# SCH_NetStream_Caravel.net
KiCad netlist of a schematic drawn in EasyEDA
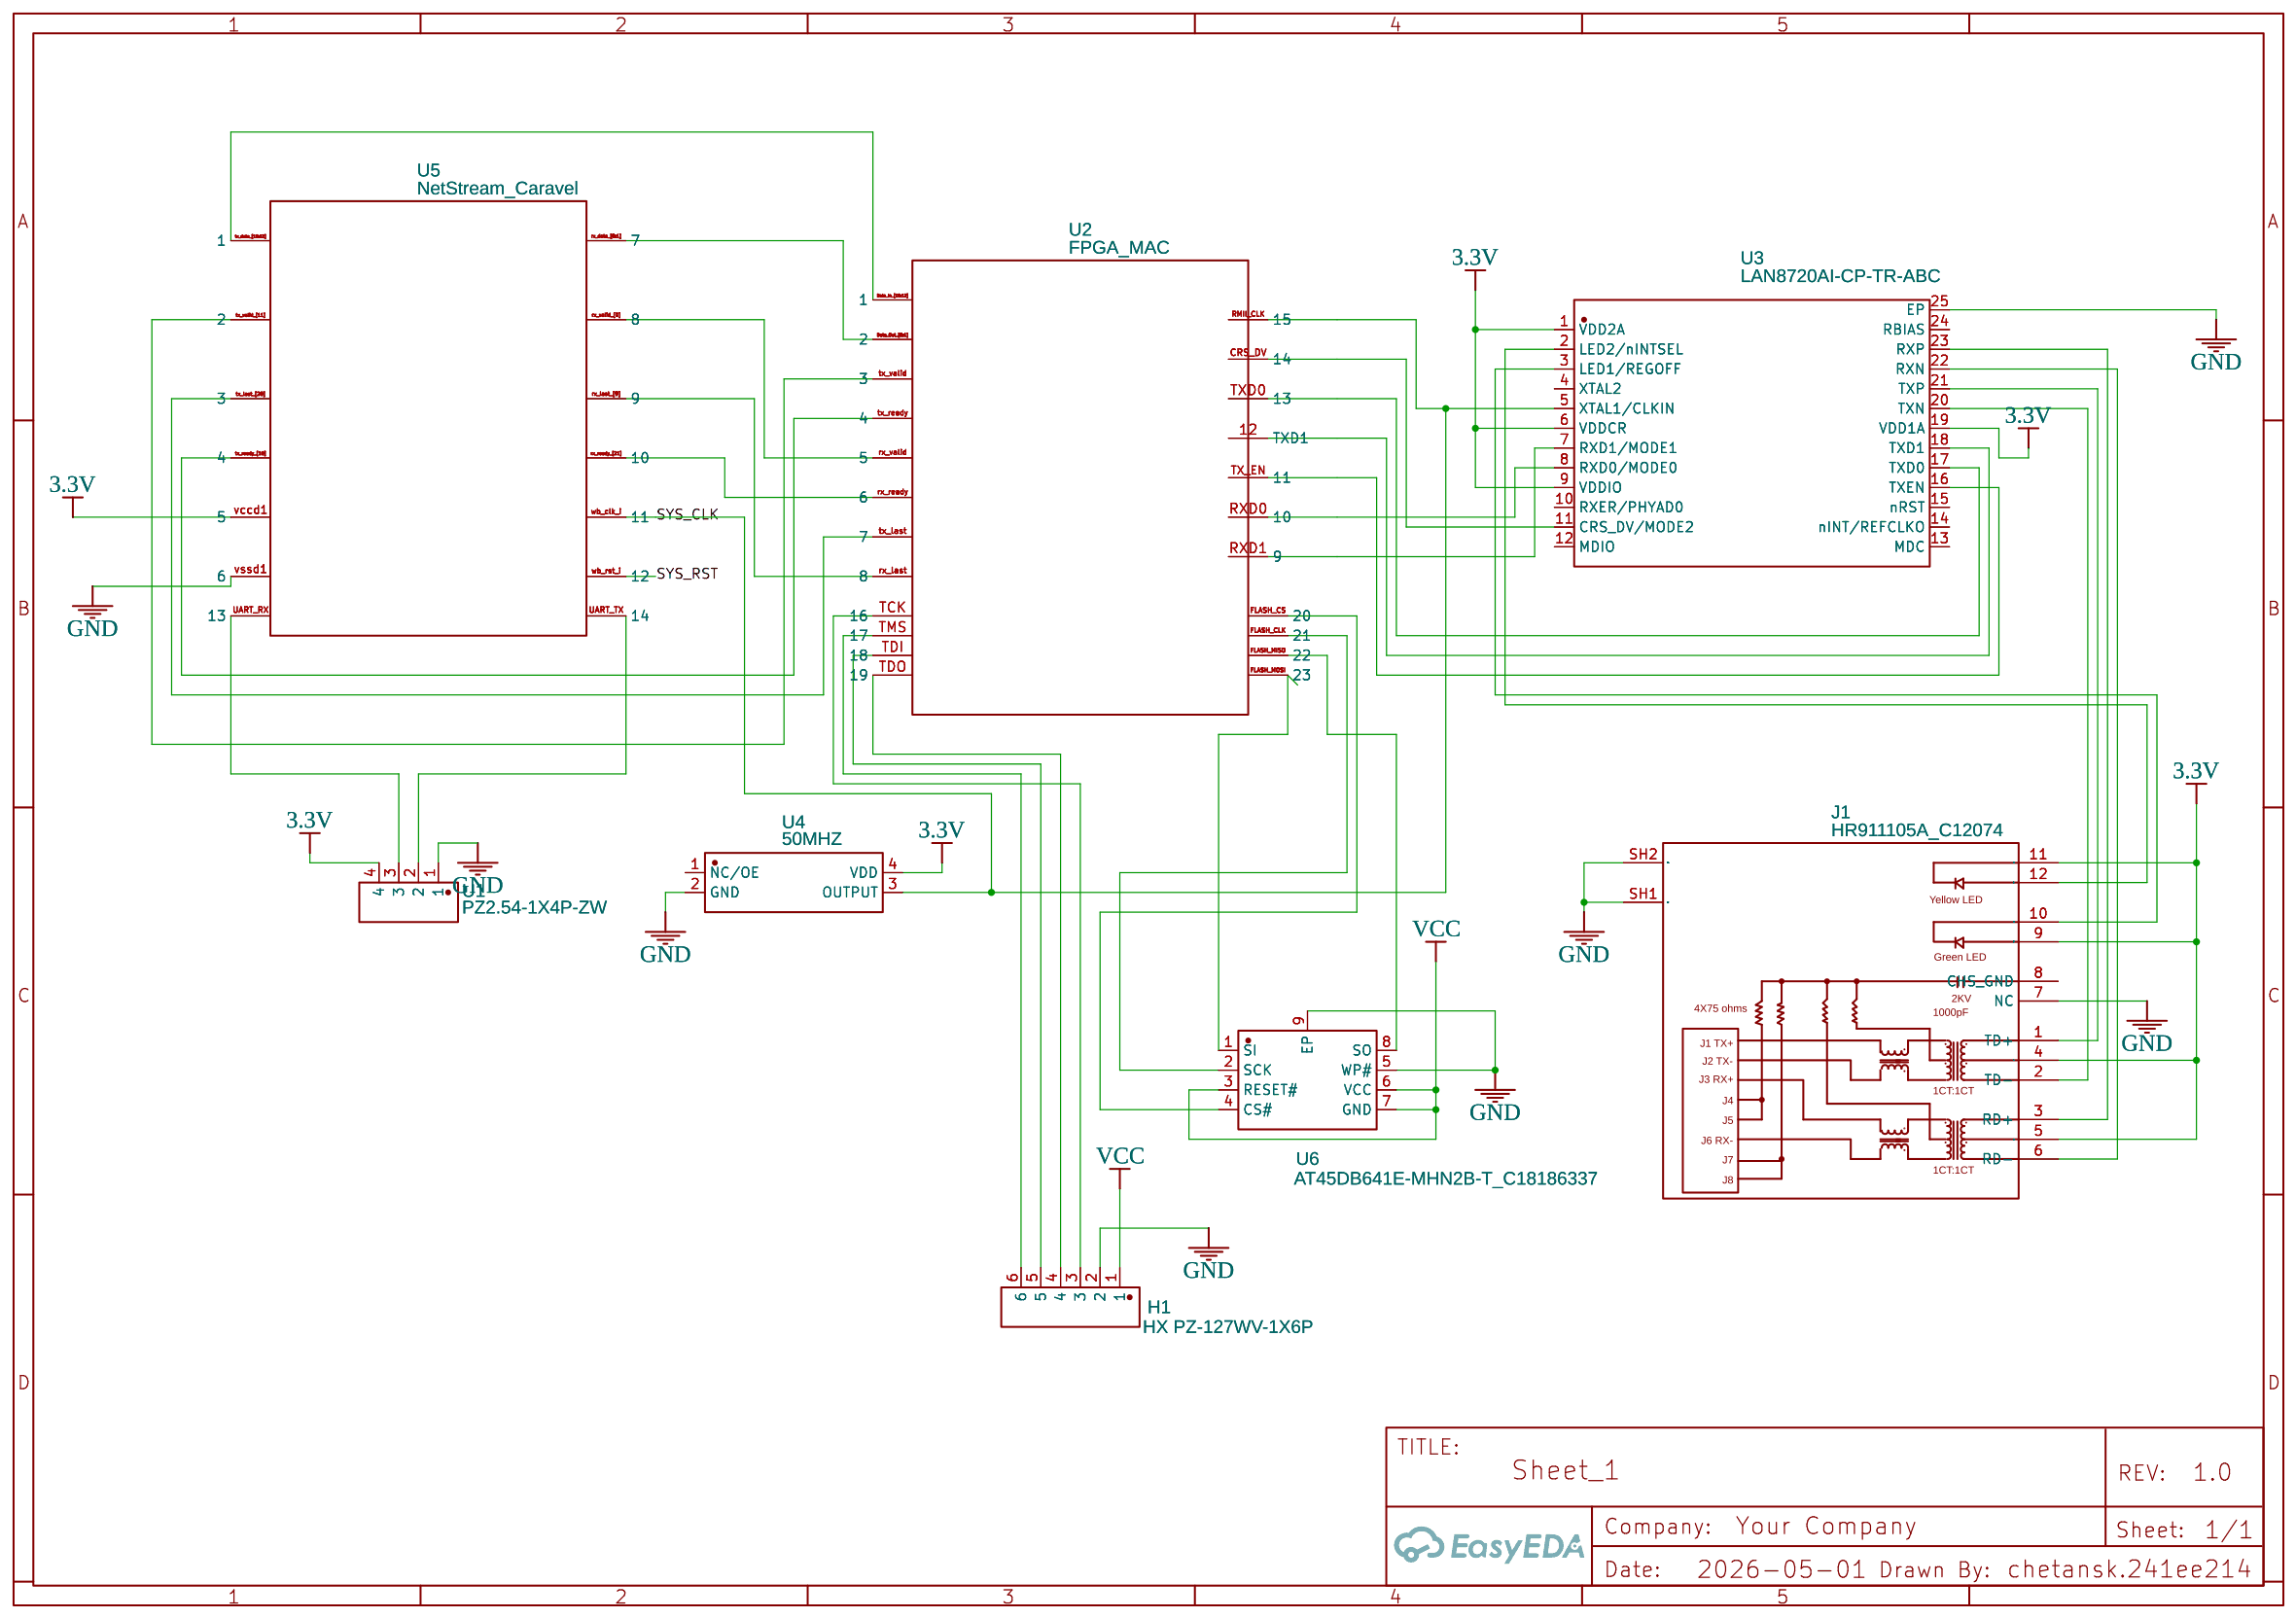
[diagram p0: schematic sheet]

(export (version "E")
  (design (tool "Eeschema 10.0.6"))
  (components
    (comp (ref "H1")
      (value "HX PZ-127WV-1X6P")
      (fields
        (field (name "Manufacturer Part") "HX PZ-127WV-1x6P")
        (field (name "Manufacturer") "hanxia(韩下)")
      )
      (libsource (lib "") (part "HX PZ-127WV-1X6P"))
    )
    (comp (ref "J1")
      (value "HR911105A_C12074")
      (fields (field (name "Manufacturer Part") "HR911105A") (field (name "Manufacturer") "HANRUN(汉仁)"))
      (libsource (lib "") (part "HR911105A_C12074"))
    )
    (comp (ref "U1") (value "PZ2.54-1X4P-ZW") (libsource (lib "") (part "PZ2.54-1X4P-ZW")))
    (comp (ref "U2") (value "FPGA_MAC") (libsource (lib "") (part "FPGA_MAC")))
    (comp (ref "U3")
      (value "LAN8720AI-CP-TR-ABC")
      (fields (field (name "Manufacturer") "MICROCHIP(美国微芯)"))
      (libsource (lib "") (part "LAN8720AI-CP-TR-ABC"))
    )
    (comp (ref "U4")
      (value "50MHZ")
      (fields (field (name "Manufacturer Part") "50MHz"))
      (libsource (lib "") (part "50MHZ"))
    )
    (comp (ref "U5") (value "NetStream_Caravel") (libsource (lib "") (part "NetStream_Caravel")))
    (comp (ref "U6")
      (value "AT45DB641E-MHN2B-T_C18186337")
      (fields
        (field (name "Manufacturer Part") "AT45DB641E-MHN2B-T")
        (field (name "Manufacturer") "RENESAS(瑞萨)/IDT")
      )
      (libsource (lib "") (part "AT45DB641E-MHN2B-T_C18186337"))
    )
  )
  (nets
    (net (code "1") (name "/SYS_CLK") (class "Default")
      (node (ref "U3") (pin "5") (pinfunction "XTAL1/CLKIN_5") (pintype "unspecified"))
      (node (ref "U4") (pin "3") (pinfunction "OUTPUT_3") (pintype "unspecified"))
    )
    (net (code "3") (name "3.3V") (class "Default")
      (node (ref "J1") (pin "11") (pinfunction "11_11") (pintype "unspecified"))
      (node (ref "J1") (pin "4") (pinfunction "4_4") (pintype "unspecified"))
      (node (ref "J1") (pin "5") (pinfunction "5_5") (pintype "unspecified"))
      (node (ref "J1") (pin "9") (pinfunction "9_9") (pintype "unspecified"))
      (node (ref "U1") (pin "4") (pinfunction "4_4") (pintype "unspecified"))
      (node (ref "U3") (pin "1") (pinfunction "VDD2A_1") (pintype "unspecified"))
      (node (ref "U3") (pin "19") (pinfunction "VDD1A_19") (pintype "unspecified"))
      (node (ref "U3") (pin "6") (pinfunction "VDDCR_6") (pintype "unspecified"))
      (node (ref "U3") (pin "9") (pinfunction "VDDIO_9") (pintype "unspecified"))
      (node (ref "U4") (pin "4") (pinfunction "VDD_4") (pintype "unspecified"))
    )
    (net (code "4") (name "GND") (class "Default")
      (node (ref "H1") (pin "2") (pinfunction "2_2") (pintype "unspecified"))
      (node (ref "J1") (pin "7") (pinfunction "NC_7") (pintype "unspecified"))
      (node (ref "J1") (pin "SH1") (pinfunction "SH1_SH1") (pintype "unspecified"))
      (node (ref "J1") (pin "SH2") (pinfunction "SH2_SH2") (pintype "unspecified"))
      (node (ref "U1") (pin "1") (pinfunction "1_1") (pintype "unspecified"))
      (node (ref "U3") (pin "25") (pinfunction "EP_25") (pintype "unspecified"))
      (node (ref "U4") (pin "2") (pinfunction "GND_2") (pintype "unspecified"))
      (node (ref "U6") (pin "5") (pinfunction "WP#_5") (pintype "unspecified"))
      (node (ref "U6") (pin "9") (pinfunction "EP_9") (pintype "unspecified"))
    )
    (net (code "5") (name "Net-(J1-RD+)") (class "Default")
      (node (ref "J1") (pin "3") (pinfunction "RD+_3") (pintype "unspecified"))
      (node (ref "U3") (pin "23") (pinfunction "RXP_23") (pintype "unspecified"))
    )
    (net (code "6") (name "Net-(J1-RD-)") (class "Default")
      (node (ref "J1") (pin "6") (pinfunction "RD-_6") (pintype "unspecified"))
      (node (ref "U3") (pin "22") (pinfunction "RXN_22") (pintype "unspecified"))
    )
    (net (code "7") (name "Net-(J1-TD+)") (class "Default")
      (node (ref "J1") (pin "1") (pinfunction "TD+_1") (pintype "unspecified"))
      (node (ref "U3") (pin "21") (pinfunction "TXP_21") (pintype "unspecified"))
    )
    (net (code "8") (name "Net-(J1-TD-)") (class "Default")
      (node (ref "J1") (pin "2") (pinfunction "TD-_2") (pintype "unspecified"))
      (node (ref "U3") (pin "20") (pinfunction "TXN_20") (pintype "unspecified"))
    )
    (net (code "9") (name "Net-(U3-LED1{slash}REGOFF)") (class "Default")
      (node (ref "J1") (pin "10") (pinfunction "10_10") (pintype "unspecified"))
      (node (ref "U3") (pin "3") (pinfunction "LED1/REGOFF_3") (pintype "unspecified"))
    )
    (net (code "10") (name "Net-(U3-LED2{slash}nINTSEL)") (class "Default")
      (node (ref "J1") (pin "12") (pinfunction "12_12") (pintype "unspecified"))
      (node (ref "U3") (pin "2") (pinfunction "LED2/nINTSEL_2") (pintype "unspecified"))
    )
    (net (code "11") (name "VCC") (class "Default")
      (node (ref "H1") (pin "1") (pinfunction "1_1") (pintype "unspecified"))
      (node (ref "U6") (pin "3") (pinfunction "RESET#_3") (pintype "unspecified"))
      (node (ref "U6") (pin "6") (pinfunction "VCC_6") (pintype "unspecified"))
      (node (ref "U6") (pin "7") (pinfunction "GND_7") (pintype "unspecified"))
    )
    (net (code "12") (name "unconnected-(H1-Pad3)") (class "Default")
      (node (ref "H1") (pin "3") (pinfunction "3_3") (pintype "unspecified"))
    )
    (net (code "13") (name "unconnected-(H1-Pad4)") (class "Default")
      (node (ref "H1") (pin "4") (pinfunction "4_4") (pintype "unspecified"))
    )
    (net (code "14") (name "unconnected-(H1-Pad5)") (class "Default")
      (node (ref "H1") (pin "5") (pinfunction "5_5") (pintype "unspecified"))
    )
    (net (code "15") (name "unconnected-(H1-Pad6)") (class "Default")
      (node (ref "H1") (pin "6") (pinfunction "6_6") (pintype "unspecified"))
    )
    (net (code "16") (name "unconnected-(J1-CHS_GND-Pad8)") (class "Default")
      (node (ref "J1") (pin "8") (pinfunction "CHS_GND_8") (pintype "unspecified"))
    )
    (net (code "17") (name "unconnected-(U1-Pad2)") (class "Default")
      (node (ref "U1") (pin "2") (pinfunction "2_2") (pintype "unspecified"))
    )
    (net (code "18") (name "unconnected-(U1-Pad3)") (class "Default")
      (node (ref "U1") (pin "3") (pinfunction "3_3") (pintype "unspecified"))
    )
    (net (code "19") (name "unconnected-(U2-1-PadData_In_[19:12])") (class "Default")
      (node (ref "U2") (pin "Data_In_[19:12]") (pinfunction "1_Data_In_[19:12]") (pintype "unspecified"))
    )
    (net (code "20") (name "unconnected-(U2-2-PadData_Out_[8:1])") (class "Default")
      (node (ref "U2") (pin "Data_Out_[8:1]") (pinfunction "2_Data_Out_[8:1]") (pintype "unspecified"))
    )
    (net (code "21") (name "unconnected-(U2-3-Padtx_valid)") (class "Default")
      (node (ref "U2") (pin "tx_valid") (pinfunction "3_tx_valid") (pintype "unspecified"))
    )
    (net (code "22") (name "unconnected-(U2-4-Padtx_ready)") (class "Default")
      (node (ref "U2") (pin "tx_ready") (pinfunction "4_tx_ready") (pintype "unspecified"))
    )
    (net (code "23") (name "unconnected-(U2-5-Padrx_valid)") (class "Default")
      (node (ref "U2") (pin "rx_valid") (pinfunction "5_rx_valid") (pintype "unspecified"))
    )
    (net (code "24") (name "unconnected-(U2-6-Padrx_ready)") (class "Default")
      (node (ref "U2") (pin "rx_ready") (pinfunction "6_rx_ready") (pintype "unspecified"))
    )
    (net (code "25") (name "unconnected-(U2-7-Padtx_last)") (class "Default")
      (node (ref "U2") (pin "tx_last") (pinfunction "7_tx_last") (pintype "unspecified"))
    )
    (net (code "26") (name "unconnected-(U2-8-Padrx_last)") (class "Default")
      (node (ref "U2") (pin "rx_last") (pinfunction "8_rx_last") (pintype "unspecified"))
    )
    (net (code "27") (name "unconnected-(U2-9-PadRXD1)") (class "Default")
      (node (ref "U2") (pin "RXD1") (pinfunction "9_RXD1") (pintype "unspecified"))
    )
    (net (code "28") (name "unconnected-(U2-10-PadRXD0)") (class "Default")
      (node (ref "U2") (pin "RXD0") (pinfunction "10_RXD0") (pintype "unspecified"))
    )
    (net (code "29") (name "unconnected-(U2-11-PadTX_EN)") (class "Default")
      (node (ref "U2") (pin "TX_EN") (pinfunction "11_TX_EN") (pintype "unspecified"))
    )
    (net (code "30") (name "unconnected-(U2-13-PadTXD0)") (class "Default")
      (node (ref "U2") (pin "TXD0") (pinfunction "13_TXD0") (pintype "unspecified"))
    )
    (net (code "31") (name "unconnected-(U2-14-PadCRS_DV)") (class "Default")
      (node (ref "U2") (pin "CRS_DV") (pinfunction "14_CRS_DV") (pintype "unspecified"))
    )
    (net (code "32") (name "unconnected-(U2-15-PadRMII_CLK)") (class "Default")
      (node (ref "U2") (pin "RMII_CLK") (pinfunction "15_RMII_CLK") (pintype "unspecified"))
    )
    (net (code "33") (name "unconnected-(U2-16-PadTCK)") (class "Default")
      (node (ref "U2") (pin "TCK") (pinfunction "16_TCK") (pintype "unspecified"))
    )
    (net (code "34") (name "unconnected-(U2-17-PadTMS)") (class "Default")
      (node (ref "U2") (pin "TMS") (pinfunction "17_TMS") (pintype "unspecified"))
    )
    (net (code "35") (name "unconnected-(U2-18-PadTDI)") (class "Default")
      (node (ref "U2") (pin "TDI") (pinfunction "18_TDI") (pintype "unspecified"))
    )
    (net (code "36") (name "unconnected-(U2-19-PadTDO)") (class "Default")
      (node (ref "U2") (pin "TDO") (pinfunction "19_TDO") (pintype "unspecified"))
    )
    (net (code "37") (name "unconnected-(U2-20-PadFLASH_CS)") (class "Default")
      (node (ref "U2") (pin "FLASH_CS") (pinfunction "20_FLASH_CS") (pintype "unspecified"))
    )
    (net (code "38") (name "unconnected-(U2-21-PadFLASH_CLK)") (class "Default")
      (node (ref "U2") (pin "FLASH_CLK") (pinfunction "21_FLASH_CLK") (pintype "unspecified"))
    )
    (net (code "39") (name "unconnected-(U2-22-PadFLASH_MISO)") (class "Default")
      (node (ref "U2") (pin "FLASH_MISO") (pinfunction "22_FLASH_MISO") (pintype "unspecified"))
    )
    (net (code "40") (name "unconnected-(U2-23-PadFLASH_MOSI)") (class "Default")
      (node (ref "U2") (pin "FLASH_MOSI") (pinfunction "23_FLASH_MOSI") (pintype "unspecified"))
    )
    (net (code "41") (name "unconnected-(U2-TXD1-Pad12)") (class "Default")
      (node (ref "U2") (pin "12") (pinfunction "TXD1_12") (pintype "unspecified"))
    )
    (net (code "42") (name "unconnected-(U3-CRS_DV{slash}MODE2-Pad11)") (class "Default")
      (node (ref "U3") (pin "11") (pinfunction "CRS_DV/MODE2_11") (pintype "unspecified"))
    )
    (net (code "43") (name "unconnected-(U3-MDC-Pad13)") (class "Default")
      (node (ref "U3") (pin "13") (pinfunction "MDC_13") (pintype "unspecified"))
    )
    (net (code "44") (name "unconnected-(U3-MDIO-Pad12)") (class "Default")
      (node (ref "U3") (pin "12") (pinfunction "MDIO_12") (pintype "unspecified"))
    )
    (net (code "45") (name "unconnected-(U3-RBIAS-Pad24)") (class "Default")
      (node (ref "U3") (pin "24") (pinfunction "RBIAS_24") (pintype "unspecified"))
    )
    (net (code "46") (name "unconnected-(U3-RXD0{slash}MODE0-Pad8)") (class "Default")
      (node (ref "U3") (pin "8") (pinfunction "RXD0/MODE0_8") (pintype "unspecified"))
    )
    (net (code "47") (name "unconnected-(U3-RXD1{slash}MODE1-Pad7)") (class "Default")
      (node (ref "U3") (pin "7") (pinfunction "RXD1/MODE1_7") (pintype "unspecified"))
    )
    (net (code "48") (name "unconnected-(U3-RXER{slash}PHYAD0-Pad10)") (class "Default")
      (node (ref "U3") (pin "10") (pinfunction "RXER/PHYAD0_10") (pintype "unspecified"))
    )
    (net (code "49") (name "unconnected-(U3-TXD0-Pad17)") (class "Default")
      (node (ref "U3") (pin "17") (pinfunction "TXD0_17") (pintype "unspecified"))
    )
    (net (code "50") (name "unconnected-(U3-TXD1-Pad18)") (class "Default")
      (node (ref "U3") (pin "18") (pinfunction "TXD1_18") (pintype "unspecified"))
    )
    (net (code "51") (name "unconnected-(U3-TXEN-Pad16)") (class "Default")
      (node (ref "U3") (pin "16") (pinfunction "TXEN_16") (pintype "unspecified"))
    )
    (net (code "52") (name "unconnected-(U3-XTAL2-Pad4)") (class "Default")
      (node (ref "U3") (pin "4") (pinfunction "XTAL2_4") (pintype "unspecified"))
    )
    (net (code "53") (name "unconnected-(U3-nINT{slash}REFCLKO-Pad14)") (class "Default")
      (node (ref "U3") (pin "14") (pinfunction "nINT/REFCLKO_14") (pintype "unspecified"))
    )
    (net (code "54") (name "unconnected-(U3-nRST-Pad15)") (class "Default")
      (node (ref "U3") (pin "15") (pinfunction "nRST_15") (pintype "unspecified"))
    )
    (net (code "55") (name "unconnected-(U4-NC{slash}OE-Pad1)") (class "Default")
      (node (ref "U4") (pin "1") (pinfunction "NC/OE_1") (pintype "unspecified"))
    )
    (net (code "56") (name "unconnected-(U5-1-Padtx_data_[19:12])") (class "Default")
      (node (ref "U5") (pin "tx_data_[19:12]") (pinfunction "1_tx_data_[19:12]") (pintype "unspecified"))
    )
    (net (code "57") (name "unconnected-(U5-2-Padtx_valid_[11])") (class "Default")
      (node (ref "U5") (pin "tx_valid_[11]") (pinfunction "2_tx_valid_[11]") (pintype "unspecified"))
    )
    (net (code "58") (name "unconnected-(U5-3-Padtx_last_[20])") (class "Default")
      (node (ref "U5") (pin "tx_last_[20]") (pinfunction "3_tx_last_[20]") (pintype "unspecified"))
    )
    (net (code "59") (name "unconnected-(U5-4-Padtx_ready_[10])") (class "Default")
      (node (ref "U5") (pin "tx_ready_[10]") (pinfunction "4_tx_ready_[10]") (pintype "unspecified"))
    )
    (net (code "60") (name "unconnected-(U5-5-Padvccd1)") (class "Default")
      (node (ref "U5") (pin "vccd1") (pinfunction "5_vccd1") (pintype "unspecified"))
    )
    (net (code "61") (name "unconnected-(U5-6-Padvssd1)") (class "Default")
      (node (ref "U5") (pin "vssd1") (pinfunction "6_vssd1") (pintype "unspecified"))
    )
    (net (code "62") (name "unconnected-(U5-7-Padrx_data_[8:1])") (class "Default")
      (node (ref "U5") (pin "rx_data_[8:1]") (pinfunction "7_rx_data_[8:1]") (pintype "unspecified"))
    )
    (net (code "63") (name "unconnected-(U5-8-Padrx_valid_[0])") (class "Default")
      (node (ref "U5") (pin "rx_valid_[0]") (pinfunction "8_rx_valid_[0]") (pintype "unspecified"))
    )
    (net (code "64") (name "unconnected-(U5-9-Padrx_last_[9])") (class "Default")
      (node (ref "U5") (pin "rx_last_[9]") (pinfunction "9_rx_last_[9]") (pintype "unspecified"))
    )
    (net (code "65") (name "unconnected-(U5-10-Padrx_ready_[21])") (class "Default")
      (node (ref "U5") (pin "rx_ready_[21]") (pinfunction "10_rx_ready_[21]") (pintype "unspecified"))
    )
    (net (code "66") (name "unconnected-(U5-11-Padwb_clk_i)") (class "Default")
      (node (ref "U5") (pin "wb_clk_i") (pinfunction "11_wb_clk_i") (pintype "unspecified"))
    )
    (net (code "67") (name "unconnected-(U5-12-Padwb_rst_i)") (class "Default")
      (node (ref "U5") (pin "wb_rst_i") (pinfunction "12_wb_rst_i") (pintype "unspecified"))
    )
    (net (code "68") (name "unconnected-(U5-13-PadUART_RX)") (class "Default")
      (node (ref "U5") (pin "UART_RX") (pinfunction "13_UART_RX") (pintype "unspecified"))
    )
    (net (code "69") (name "unconnected-(U5-14-PadUART_TX)") (class "Default")
      (node (ref "U5") (pin "UART_TX") (pinfunction "14_UART_TX") (pintype "unspecified"))
    )
    (net (code "70") (name "unconnected-(U6-CS#-Pad4)") (class "Default")
      (node (ref "U6") (pin "4") (pinfunction "CS#_4") (pintype "unspecified"))
    )
    (net (code "71") (name "unconnected-(U6-SCK-Pad2)") (class "Default")
      (node (ref "U6") (pin "2") (pinfunction "SCK_2") (pintype "unspecified"))
    )
    (net (code "72") (name "unconnected-(U6-SI-Pad1)") (class "Default")
      (node (ref "U6") (pin "1") (pinfunction "SI_1") (pintype "unspecified"))
    )
    (net (code "73") (name "unconnected-(U6-SO-Pad8)") (class "Default")
      (node (ref "U6") (pin "8") (pinfunction "SO_8") (pintype "unspecified"))
    )
  )
)
